# Shield_Bot.net
KiCad netlist of a schematic drawn in EAGLE
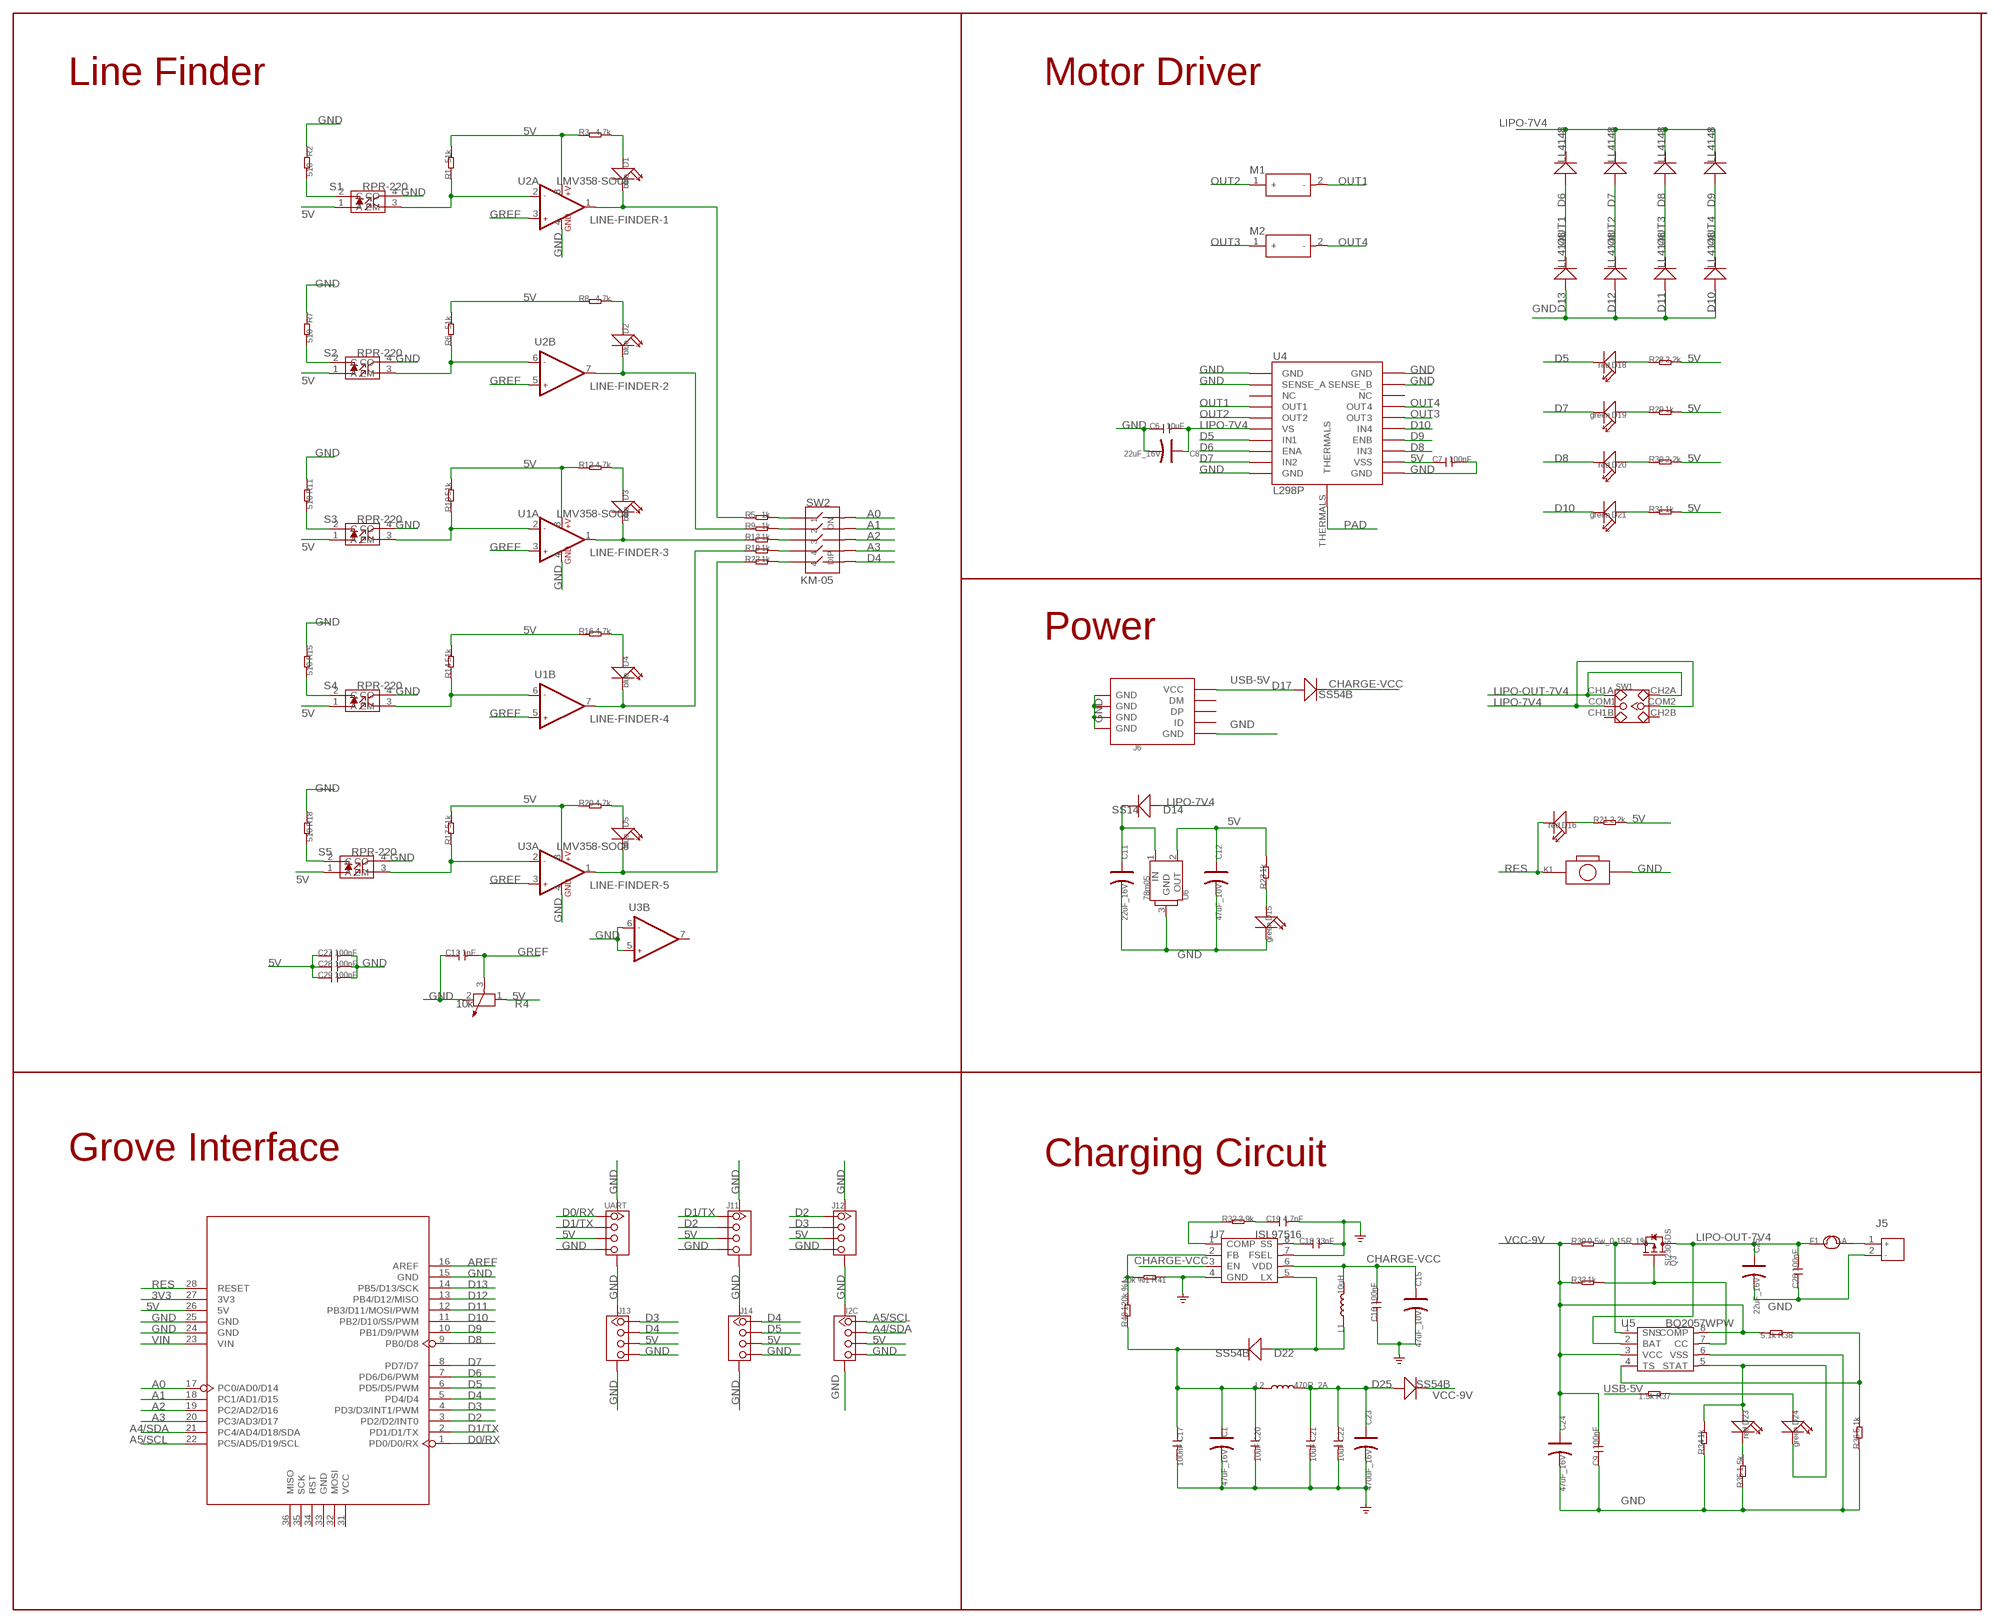
[diagram p0: schematic, sheet 1]

(export (version "E")
  (design (tool "Eeschema 10.0.6"))
  (components
    (comp (ref "C1")
      (value "47uF_16V")
      (footprint "eagle-import:AVX-C")
      (libsource (lib "eagle-import") (part "CAP-AVX-C"))
    )
    (comp (ref "C6")
      (value "10uF")
      (footprint "eagle-import:C0603")
      (libsource (lib "eagle-import") (part "C-0603"))
    )
    (comp (ref "C7")
      (value "100nF")
      (footprint "eagle-import:C0603")
      (libsource (lib "eagle-import") (part "C-0603"))
    )
    (comp (ref "C8")
      (value "22uF_16V")
      (footprint "eagle-import:AVX-B")
      (libsource (lib "eagle-import") (part "CAP-AVX-B"))
    )
    (comp (ref "C9")
      (value "100nF")
      (footprint "eagle-import:C0603")
      (libsource (lib "eagle-import") (part "C-0603"))
    )
    (comp (ref "C11")
      (value "22uF_16V")
      (footprint "eagle-import:AVX-B")
      (libsource (lib "eagle-import") (part "CAP-AVX-B"))
    )
    (comp (ref "C12")
      (value "47uF_10V")
      (footprint "eagle-import:AVX-B")
      (libsource (lib "eagle-import") (part "CAP-AVX-B"))
    )
    (comp (ref "C13")
      (value "1nF")
      (footprint "eagle-import:C0603")
      (libsource (lib "eagle-import") (part "C-0603"))
    )
    (comp (ref "C15")
      (value "47uF_10V")
      (footprint "eagle-import:AVX-B")
      (libsource (lib "eagle-import") (part "CAP-AVX-B"))
    )
    (comp (ref "C16")
      (value "100nF")
      (footprint "eagle-import:C0603")
      (libsource (lib "eagle-import") (part "C-0603"))
    )
    (comp (ref "C17")
      (value "100nF")
      (footprint "eagle-import:C0603")
      (libsource (lib "eagle-import") (part "C-0603"))
    )
    (comp (ref "C18")
      (value "33nF")
      (footprint "eagle-import:C0603")
      (libsource (lib "eagle-import") (part "C-0603"))
    )
    (comp (ref "C19")
      (value "4.7nF")
      (footprint "eagle-import:C0603")
      (libsource (lib "eagle-import") (part "C-0603"))
    )
    (comp (ref "C20")
      (value "10uF")
      (footprint "eagle-import:C0603")
      (libsource (lib "eagle-import") (part "C-0603"))
    )
    (comp (ref "C21")
      (value "10uF")
      (footprint "eagle-import:C0603")
      (libsource (lib "eagle-import") (part "C-0603"))
    )
    (comp (ref "C22")
      (value "10uF")
      (footprint "eagle-import:C0603")
      (libsource (lib "eagle-import") (part "C-0603"))
    )
    (comp (ref "C23")
      (value "470uF_16V")
      (footprint "eagle-import:AVX-E")
      (libsource (lib "eagle-import") (part "CAP-AVX-E"))
    )
    (comp (ref "C24")
      (value "47uF_16V")
      (footprint "eagle-import:AVX-C")
      (libsource (lib "eagle-import") (part "CAP-AVX-C"))
    )
    (comp (ref "C25")
      (value "22uF_16V")
      (footprint "eagle-import:AVX-B")
      (libsource (lib "eagle-import") (part "CAP-AVX-B"))
    )
    (comp (ref "C26")
      (value "100nF")
      (footprint "eagle-import:C0603")
      (libsource (lib "eagle-import") (part "C-0603"))
    )
    (comp (ref "C27")
      (value "100nF")
      (footprint "eagle-import:C0603")
      (libsource (lib "eagle-import") (part "C-0603"))
    )
    (comp (ref "C28")
      (value "100nF")
      (footprint "eagle-import:C0603")
      (libsource (lib "eagle-import") (part "C-0603"))
    )
    (comp (ref "C29")
      (value "100nF")
      (footprint "eagle-import:C0603")
      (libsource (lib "eagle-import") (part "C-0603"))
    )
    (comp (ref "D1")
      (value "blue")
      (footprint "eagle-import:LED-0603")
      (libsource (lib "eagle-import") (part "LED'0603'"))
    )
    (comp (ref "D2")
      (value "blue")
      (footprint "eagle-import:LED-0603")
      (libsource (lib "eagle-import") (part "LED'0603'"))
    )
    (comp (ref "D3")
      (value "blue")
      (footprint "eagle-import:LED-0603")
      (libsource (lib "eagle-import") (part "LED'0603'"))
    )
    (comp (ref "D4")
      (value "blue")
      (footprint "eagle-import:LED-0603")
      (libsource (lib "eagle-import") (part "LED'0603'"))
    )
    (comp (ref "D5")
      (value "blue")
      (footprint "eagle-import:LED-0603")
      (libsource (lib "eagle-import") (part "LED'0603'"))
    )
    (comp (ref "D6")
      (value "LL4148")
      (footprint "eagle-import:SOD123")
      (libsource (lib "eagle-import") (part "D'1206'"))
    )
    (comp (ref "D7")
      (value "LL4148")
      (footprint "eagle-import:SOD123")
      (libsource (lib "eagle-import") (part "D'1206'"))
    )
    (comp (ref "D8")
      (value "LL4148")
      (footprint "eagle-import:SOD123")
      (libsource (lib "eagle-import") (part "D'1206'"))
    )
    (comp (ref "D9")
      (value "LL4148")
      (footprint "eagle-import:SOD123")
      (libsource (lib "eagle-import") (part "D'1206'"))
    )
    (comp (ref "D10")
      (value "LL4148")
      (footprint "eagle-import:SOD123")
      (libsource (lib "eagle-import") (part "D'1206'"))
    )
    (comp (ref "D11")
      (value "LL4148")
      (footprint "eagle-import:SOD123")
      (libsource (lib "eagle-import") (part "D'1206'"))
    )
    (comp (ref "D12")
      (value "LL4148")
      (footprint "eagle-import:SOD123")
      (libsource (lib "eagle-import") (part "D'1206'"))
    )
    (comp (ref "D13")
      (value "LL4148")
      (footprint "eagle-import:SOD123")
      (libsource (lib "eagle-import") (part "D'1206'"))
    )
    (comp (ref "D14")
      (value "SS14")
      (footprint "eagle-import:D2010")
      (libsource (lib "eagle-import") (part "D'SMA'"))
    )
    (comp (ref "D15")
      (value "green")
      (footprint "eagle-import:LED-0603")
      (libsource (lib "eagle-import") (part "LED'0603'"))
    )
    (comp (ref "D16")
      (value "red")
      (footprint "eagle-import:LED-0603")
      (libsource (lib "eagle-import") (part "LED'0603'"))
    )
    (comp (ref "D17")
      (value "SS54B")
      (footprint "eagle-import:SMB")
      (libsource (lib "eagle-import") (part "D'MBRS240LT3'"))
    )
    (comp (ref "D18")
      (value "red")
      (footprint "eagle-import:LED-0603")
      (libsource (lib "eagle-import") (part "LED'0603'"))
    )
    (comp (ref "D19")
      (value "green")
      (footprint "eagle-import:LED-0603")
      (libsource (lib "eagle-import") (part "LED'0603'"))
    )
    (comp (ref "D20")
      (value "red")
      (footprint "eagle-import:LED-0603")
      (libsource (lib "eagle-import") (part "LED'0603'"))
    )
    (comp (ref "D21")
      (value "green")
      (footprint "eagle-import:LED-0603")
      (libsource (lib "eagle-import") (part "LED'0603'"))
    )
    (comp (ref "D22")
      (value "SS54B")
      (footprint "eagle-import:SMB")
      (libsource (lib "eagle-import") (part "D'MBRS240LT3'"))
    )
    (comp (ref "D23")
      (value "red")
      (footprint "eagle-import:LED-0603")
      (libsource (lib "eagle-import") (part "LED'0603'"))
    )
    (comp (ref "D24")
      (value "green")
      (footprint "eagle-import:LED-0603")
      (libsource (lib "eagle-import") (part "LED'0603'"))
    )
    (comp (ref "D25")
      (value "SS54B")
      (footprint "eagle-import:SMB")
      (libsource (lib "eagle-import") (part "D'MBRS240LT3'"))
    )
    (comp (ref "F1")
      (value "1A")
      (footprint "eagle-import:1812")
      (libsource (lib "eagle-import") (part "FUSE"))
    )
    (comp (ref "I2C")
      (value "TWIG-4P-2.0-SMD-FEMALE-REINFORCE'90D'")
      (footprint "eagle-import:4P-SMD-2.0-90D")
      (libsource (lib "eagle-import") (part "TWIG-4P-2.0-SMD-FEMALE-REINFORCE'90D'"))
    )
    (comp (ref "J5")
      (value "JACK-JST-2P-PW'2.0'")
      (footprint "eagle-import:JST-2.0")
      (libsource (lib "eagle-import") (part "JACK-JST-2P-PW'2.0'"))
    )
    (comp (ref "J6")
      (value "USB-MINIUSB-5P-STRONG")
      (footprint "eagle-import:MINI-SMD-5P")
      (libsource (lib "eagle-import") (part "USB-MINIUSB-5P-STRONG"))
    )
    (comp (ref "J11")
      (value "TWIG-4P-2.0-SMD-FEMALE-REINFORCE'90D'")
      (footprint "eagle-import:4P-SMD-2.0-90D")
      (libsource (lib "eagle-import") (part "TWIG-4P-2.0-SMD-FEMALE-REINFORCE'90D'"))
    )
    (comp (ref "J12")
      (value "TWIG-4P-2.0-SMD-FEMALE-REINFORCE'90D'")
      (footprint "eagle-import:4P-SMD-2.0-90D")
      (libsource (lib "eagle-import") (part "TWIG-4P-2.0-SMD-FEMALE-REINFORCE'90D'"))
    )
    (comp (ref "J13")
      (value "TWIG-4P-2.0-SMD-FEMALE-REINFORCE'90D'")
      (footprint "eagle-import:4P-SMD-2.0-90D")
      (libsource (lib "eagle-import") (part "TWIG-4P-2.0-SMD-FEMALE-REINFORCE'90D'"))
    )
    (comp (ref "J14")
      (value "TWIG-4P-2.0-SMD-FEMALE-REINFORCE'90D'")
      (footprint "eagle-import:4P-SMD-2.0-90D")
      (libsource (lib "eagle-import") (part "TWIG-4P-2.0-SMD-FEMALE-REINFORCE'90D'"))
    )
    (comp (ref "K1")
      (value "BOTTON-2P-90D")
      (footprint "eagle-import:2P-7.62X3.56-90D")
      (libsource (lib "eagle-import") (part "BOTTON-2P-90D"))
    )
    (comp (ref "L1")
      (value "10uH")
      (footprint "eagle-import:2626")
      (libsource (lib "eagle-import") (part "L'IHLP-2525BD-01'"))
    )
    (comp (ref "L2")
      (value "470R_2A")
      (footprint "eagle-import:L0805")
      (libsource (lib "eagle-import") (part "L'0805'"))
    )
    (comp (ref "M1")
      (value "MOTOR-2P-PAD")
      (footprint "eagle-import:2P-SMD-27X26")
      (libsource (lib "eagle-import") (part "MOTOR-2P-PAD"))
    )
    (comp (ref "M2")
      (value "MOTOR-2P-PAD")
      (footprint "eagle-import:2P-SMD-27X26")
      (libsource (lib "eagle-import") (part "MOTOR-2P-PAD"))
    )
    (comp (ref "Q3")
      (value "SI2305DS")
      (footprint "eagle-import:SOT23")
      (libsource (lib "eagle-import") (part "MOSFET-P'SI2323CDS/SI2305DS{lt}BR{gt}'"))
    )
    (comp (ref "R1")
      (value "51k")
      (footprint "eagle-import:R0603")
      (libsource (lib "eagle-import") (part "R-0603"))
    )
    (comp (ref "R2")
      (value "510")
      (footprint "eagle-import:R0603")
      (libsource (lib "eagle-import") (part "R-0603"))
    )
    (comp (ref "R3")
      (value "4.7k")
      (footprint "eagle-import:R0603")
      (libsource (lib "eagle-import") (part "R-0603"))
    )
    (comp (ref "R4")
      (value "10k")
      (footprint "eagle-import:3P-SQUA-7X6.8")
      (libsource (lib "eagle-import") (part "R-POTENTIOMETER'3362'"))
    )
    (comp (ref "R5")
      (value "1k")
      (footprint "eagle-import:R0603")
      (libsource (lib "eagle-import") (part "R-0603"))
    )
    (comp (ref "R6")
      (value "51k")
      (footprint "eagle-import:R0603")
      (libsource (lib "eagle-import") (part "R-0603"))
    )
    (comp (ref "R7")
      (value "510")
      (footprint "eagle-import:R0603")
      (libsource (lib "eagle-import") (part "R-0603"))
    )
    (comp (ref "R8")
      (value "4.7k")
      (footprint "eagle-import:R0603")
      (libsource (lib "eagle-import") (part "R-0603"))
    )
    (comp (ref "R9")
      (value "1k")
      (footprint "eagle-import:R0603")
      (libsource (lib "eagle-import") (part "R-0603"))
    )
    (comp (ref "R10")
      (value "51k")
      (footprint "eagle-import:R0603")
      (libsource (lib "eagle-import") (part "R-0603"))
    )
    (comp (ref "R11")
      (value "510")
      (footprint "eagle-import:R0603")
      (libsource (lib "eagle-import") (part "R-0603"))
    )
    (comp (ref "R12")
      (value "4.7k")
      (footprint "eagle-import:R0603")
      (libsource (lib "eagle-import") (part "R-0603"))
    )
    (comp (ref "R13")
      (value "1k")
      (footprint "eagle-import:R0603")
      (libsource (lib "eagle-import") (part "R-0603"))
    )
    (comp (ref "R14")
      (value "51k")
      (footprint "eagle-import:R0603")
      (libsource (lib "eagle-import") (part "R-0603"))
    )
    (comp (ref "R15")
      (value "510")
      (footprint "eagle-import:R0603")
      (libsource (lib "eagle-import") (part "R-0603"))
    )
    (comp (ref "R16")
      (value "4.7k")
      (footprint "eagle-import:R0603")
      (libsource (lib "eagle-import") (part "R-0603"))
    )
    (comp (ref "R17")
      (value "51k")
      (footprint "eagle-import:R0603")
      (libsource (lib "eagle-import") (part "R-0603"))
    )
    (comp (ref "R18")
      (value "510")
      (footprint "eagle-import:R0603")
      (libsource (lib "eagle-import") (part "R-0603"))
    )
    (comp (ref "R19")
      (value "1k")
      (footprint "eagle-import:R0603")
      (libsource (lib "eagle-import") (part "R-0603"))
    )
    (comp (ref "R20")
      (value "4.7k")
      (footprint "eagle-import:R0603")
      (libsource (lib "eagle-import") (part "R-0603"))
    )
    (comp (ref "R21")
      (value "2.2k")
      (footprint "eagle-import:R0603")
      (libsource (lib "eagle-import") (part "R-0603"))
    )
    (comp (ref "R22")
      (value "1k")
      (footprint "eagle-import:R0603")
      (libsource (lib "eagle-import") (part "R-0603"))
    )
    (comp (ref "R23")
      (value "1k")
      (footprint "eagle-import:R0603")
      (libsource (lib "eagle-import") (part "R-0603"))
    )
    (comp (ref "R28")
      (value "2.2k")
      (footprint "eagle-import:R0603")
      (libsource (lib "eagle-import") (part "R-0603"))
    )
    (comp (ref "R29")
      (value "1k")
      (footprint "eagle-import:R0603")
      (libsource (lib "eagle-import") (part "R-0603"))
    )
    (comp (ref "R30")
      (value "2.2k")
      (footprint "eagle-import:R0603")
      (libsource (lib "eagle-import") (part "R-0603"))
    )
    (comp (ref "R31")
      (value "1k")
      (footprint "eagle-import:R0603")
      (libsource (lib "eagle-import") (part "R-0603"))
    )
    (comp (ref "R32")
      (value "3.9k")
      (footprint "eagle-import:R0603")
      (libsource (lib "eagle-import") (part "R-0603"))
    )
    (comp (ref "R33")
      (value "1k")
      (footprint "eagle-import:R0603")
      (libsource (lib "eagle-import") (part "R-0603"))
    )
    (comp (ref "R34")
      (value "1k")
      (footprint "eagle-import:R0603")
      (libsource (lib "eagle-import") (part "R-0603"))
    )
    (comp (ref "R35")
      (value "1.5k")
      (footprint "eagle-import:R0603")
      (libsource (lib "eagle-import") (part "R-0603"))
    )
    (comp (ref "R36")
      (value "5.1k")
      (footprint "eagle-import:R0603")
      (libsource (lib "eagle-import") (part "R-0603"))
    )
    (comp (ref "R37")
      (value "1.5k")
      (footprint "eagle-import:R0603")
      (libsource (lib "eagle-import") (part "R-0603"))
    )
    (comp (ref "R38")
      (value "5.1k")
      (footprint "eagle-import:R0603")
      (libsource (lib "eagle-import") (part "R-0603"))
    )
    (comp (ref "R39")
      (value "0.5w_0.15R 1%")
      (footprint "eagle-import:R2512")
      (libsource (lib "eagle-import") (part "R-2512"))
    )
    (comp (ref "R40")
      (value "120k %1")
      (footprint "eagle-import:R0603")
      (libsource (lib "eagle-import") (part "R-0603"))
    )
    (comp (ref "R41")
      (value "20k %1")
      (footprint "eagle-import:R0603")
      (libsource (lib "eagle-import") (part "R-0603"))
    )
    (comp (ref "S1")
      (value "RPR-220")
      (footprint "eagle-import:4P-6.4X4.9X6.5H")
      (libsource (lib "eagle-import") (part "REFLECTIVE-PHOTOSENSOR-RPR-220"))
    )
    (comp (ref "S2")
      (value "RPR-220")
      (footprint "eagle-import:4P-6.4X4.9X6.5H")
      (libsource (lib "eagle-import") (part "REFLECTIVE-PHOTOSENSOR-RPR-220"))
    )
    (comp (ref "S3")
      (value "RPR-220")
      (footprint "eagle-import:4P-6.4X4.9X6.5H")
      (libsource (lib "eagle-import") (part "REFLECTIVE-PHOTOSENSOR-RPR-220"))
    )
    (comp (ref "S4")
      (value "RPR-220")
      (footprint "eagle-import:4P-6.4X4.9X6.5H")
      (libsource (lib "eagle-import") (part "REFLECTIVE-PHOTOSENSOR-RPR-220"))
    )
    (comp (ref "S5")
      (value "RPR-220")
      (footprint "eagle-import:4P-6.4X4.9X6.5H")
      (libsource (lib "eagle-import") (part "REFLECTIVE-PHOTOSENSOR-RPR-220"))
    )
    (comp (ref "SW1")
      (value "SWITCH-2CH-6P'90D'")
      (footprint "eagle-import:6P-2CH-2.54-9.0X3.6-90D")
      (libsource (lib "eagle-import") (part "SWITCH-2CH-6P'90D'"))
    )
    (comp (ref "SW2")
      (value "KM-05")
      (footprint "eagle-import:10P-SMD-14.2X6.8")
      (libsource (lib "eagle-import") (part "SWITCH-KM-05-10P"))
    )
    (comp (ref "U1")
      (value "LMV358-SO08")
      (footprint "eagle-import:SO08")
      (libsource (lib "eagle-import") (part "LMV358-SO08"))
    )
    (comp (ref "U2")
      (value "LMV358-SO08")
      (footprint "eagle-import:SO08")
      (libsource (lib "eagle-import") (part "LMV358-SO08"))
    )
    (comp (ref "U3")
      (value "LMV358-SO08")
      (footprint "eagle-import:SO08")
      (libsource (lib "eagle-import") (part "LMV358-SO08"))
    )
    (comp (ref "U4")
      (value "L298P")
      (footprint "eagle-import:POWERSO20")
      (libsource (lib "eagle-import") (part "L298_BRIDGE_DRIVER"))
    )
    (comp (ref "U5")
      (value "BQ2057WPW")
      (footprint "eagle-import:TSSOP8")
      (libsource (lib "eagle-import") (part "BQ2057WPW"))
    )
    (comp (ref "U6")
      (value "78m05")
      (footprint "eagle-import:TO252")
      (libsource (lib "eagle-import") (part "78M05-TO252"))
    )
    (comp (ref "U7")
      (value "ISL97516")
      (footprint "eagle-import:MSOP8")
      (libsource (lib "eagle-import") (part "ISL97516"))
    )
    (comp (ref "U13")
      (value "ARDUINO")
      (footprint "eagle-import:ARDUINO")
      (libsource (lib "eagle-import") (part "ARDUINO"))
    )
    (comp (ref "UART")
      (value "TWIG-4P-2.0-SMD-FEMALE-REINFORCE'90D'")
      (footprint "eagle-import:4P-SMD-2.0-90D")
      (libsource (lib "eagle-import") (part "TWIG-4P-2.0-SMD-FEMALE-REINFORCE'90D'"))
    )
  )
  (nets
    (net (code "1") (name "/3V3") (class "Default")
      (node (ref "U13") (pin "27") (pinfunction "3V3_27") (pintype "bidirectional"))
    )
    (net (code "2") (name "/5V") (class "Default")
      (node (ref "C12") (pin "+") (pinfunction "+_+") (pintype "passive"))
      (node (ref "C27") (pin "1") (pinfunction "1_1") (pintype "passive"))
      (node (ref "C28") (pin "1") (pinfunction "1_1") (pintype "passive"))
      (node (ref "C29") (pin "1") (pinfunction "1_1") (pintype "passive"))
      (node (ref "C7") (pin "1") (pinfunction "1_1") (pintype "passive"))
      (node (ref "I2C") (pin "3") (pinfunction "3_3") (pintype "bidirectional"))
      (node (ref "J11") (pin "3") (pinfunction "3_3") (pintype "bidirectional"))
      (node (ref "J12") (pin "3") (pinfunction "3_3") (pintype "bidirectional"))
      (node (ref "J13") (pin "3") (pinfunction "3_3") (pintype "bidirectional"))
      (node (ref "J14") (pin "3") (pinfunction "3_3") (pintype "bidirectional"))
      (node (ref "R1") (pin "2") (pinfunction "2_2") (pintype "passive"))
      (node (ref "R10") (pin "2") (pinfunction "2_2") (pintype "passive"))
      (node (ref "R12") (pin "1") (pinfunction "1_1") (pintype "passive"))
      (node (ref "R14") (pin "2") (pinfunction "2_2") (pintype "passive"))
      (node (ref "R16") (pin "1") (pinfunction "1_1") (pintype "passive"))
      (node (ref "R17") (pin "2") (pinfunction "2_2") (pintype "passive"))
      (node (ref "R20") (pin "1") (pinfunction "1_1") (pintype "passive"))
      (node (ref "R21") (pin "2") (pinfunction "2_2") (pintype "passive"))
      (node (ref "R23") (pin "2") (pinfunction "2_2") (pintype "passive"))
      (node (ref "R28") (pin "2") (pinfunction "2_2") (pintype "passive"))
      (node (ref "R29") (pin "2") (pinfunction "2_2") (pintype "passive"))
      (node (ref "R3") (pin "1") (pinfunction "1_1") (pintype "passive"))
      (node (ref "R30") (pin "2") (pinfunction "2_2") (pintype "passive"))
      (node (ref "R31") (pin "2") (pinfunction "2_2") (pintype "passive"))
      (node (ref "R4") (pin "1") (pinfunction "1_1") (pintype "passive"))
      (node (ref "R6") (pin "2") (pinfunction "2_2") (pintype "passive"))
      (node (ref "R8") (pin "1") (pinfunction "1_1") (pintype "passive"))
      (node (ref "S1") (pin "1") (pinfunction "A_1") (pintype "bidirectional"))
      (node (ref "S2") (pin "1") (pinfunction "A_1") (pintype "bidirectional"))
      (node (ref "S3") (pin "1") (pinfunction "A_1") (pintype "bidirectional"))
      (node (ref "S4") (pin "1") (pinfunction "A_1") (pintype "bidirectional"))
      (node (ref "S5") (pin "1") (pinfunction "A_1") (pintype "bidirectional"))
      (node (ref "U1") (pin "8") (pinfunction "+V_8") (pintype "power_in"))
      (node (ref "U13") (pin "26") (pinfunction "5V_26") (pintype "bidirectional"))
      (node (ref "U2") (pin "8") (pinfunction "+V_8") (pintype "power_in"))
      (node (ref "U3") (pin "8") (pinfunction "+V_8") (pintype "power_in"))
      (node (ref "U4") (pin "P$12") (pinfunction "VSS_P$12") (pintype "bidirectional"))
      (node (ref "U6") (pin "2") (pinfunction "OUT_2") (pintype "bidirectional"))
      (node (ref "UART") (pin "3") (pinfunction "3_3") (pintype "bidirectional"))
    )
    (net (code "3") (name "/A0") (class "Default")
      (node (ref "SW2") (pin "10") (pinfunction "10_10") (pintype "bidirectional"))
      (node (ref "U13") (pin "17") (pinfunction "PC0/AD0/D14_17") (pintype "bidirectional"))
    )
    (net (code "4") (name "/A1") (class "Default")
      (node (ref "SW2") (pin "9") (pinfunction "9_9") (pintype "bidirectional"))
      (node (ref "U13") (pin "18") (pinfunction "PC1/AD1/D15_18") (pintype "bidirectional"))
    )
    (net (code "5") (name "/A2") (class "Default")
      (node (ref "SW2") (pin "8") (pinfunction "8_8") (pintype "bidirectional"))
      (node (ref "U13") (pin "19") (pinfunction "PC2/AD2/D16_19") (pintype "bidirectional"))
    )
    (net (code "6") (name "/A3") (class "Default")
      (node (ref "SW2") (pin "7") (pinfunction "7_7") (pintype "bidirectional"))
      (node (ref "U13") (pin "20") (pinfunction "PC3/AD3/D17_20") (pintype "bidirectional"))
    )
    (net (code "7") (name "/A4{slash}SDA") (class "Default")
      (node (ref "I2C") (pin "2") (pinfunction "2_2") (pintype "bidirectional"))
      (node (ref "U13") (pin "21") (pinfunction "PC4/AD4/D18/SDA_21") (pintype "bidirectional"))
    )
    (net (code "8") (name "/A5{slash}SCL") (class "Default")
      (node (ref "I2C") (pin "1") (pinfunction "1_1") (pintype "bidirectional"))
      (node (ref "U13") (pin "22") (pinfunction "PC5/AD5/D19/SCL_22") (pintype "bidirectional"))
    )
    (net (code "9") (name "/AREF") (class "Default")
      (node (ref "U13") (pin "16") (pinfunction "AREF_16") (pintype "bidirectional"))
    )
    (net (code "10") (name "/CHARGE-VCC") (class "Default")
      (node (ref "C15") (pin "+") (pinfunction "+_+") (pintype "passive"))
      (node (ref "C16") (pin "2") (pinfunction "2_2") (pintype "passive"))
      (node (ref "D17") (pin "-") (pinfunction "-_-") (pintype "passive"))
      (node (ref "L1") (pin "2") (pinfunction "2_2") (pintype "passive"))
      (node (ref "U7") (pin "3") (pinfunction "EN_3") (pintype "input"))
      (node (ref "U7") (pin "6") (pinfunction "VDD_6") (pintype "power_in"))
    )
    (net (code "11") (name "/D0{slash}RX") (class "Default")
      (node (ref "U13") (pin "1") (pinfunction "PD0/D0/RX_1") (pintype "bidirectional"))
      (node (ref "UART") (pin "1") (pinfunction "1_1") (pintype "bidirectional"))
    )
    (net (code "12") (name "/D1{slash}TX") (class "Default")
      (node (ref "J11") (pin "1") (pinfunction "1_1") (pintype "bidirectional"))
      (node (ref "U13") (pin "2") (pinfunction "PD1/D1/TX_2") (pintype "bidirectional"))
      (node (ref "UART") (pin "2") (pinfunction "2_2") (pintype "bidirectional"))
    )
    (net (code "13") (name "/D2") (class "Default")
      (node (ref "J11") (pin "2") (pinfunction "2_2") (pintype "bidirectional"))
      (node (ref "J12") (pin "1") (pinfunction "1_1") (pintype "bidirectional"))
      (node (ref "U13") (pin "3") (pinfunction "PD2/D2/INT0_3") (pintype "bidirectional"))
    )
    (net (code "14") (name "/D3") (class "Default")
      (node (ref "J12") (pin "2") (pinfunction "2_2") (pintype "bidirectional"))
      (node (ref "J13") (pin "1") (pinfunction "1_1") (pintype "bidirectional"))
      (node (ref "U13") (pin "4") (pinfunction "PD3/D3/INT1/PWM_4") (pintype "bidirectional"))
    )
    (net (code "15") (name "/D4") (class "Default")
      (node (ref "J13") (pin "2") (pinfunction "2_2") (pintype "bidirectional"))
      (node (ref "J14") (pin "1") (pinfunction "1_1") (pintype "bidirectional"))
      (node (ref "SW2") (pin "6") (pinfunction "6_6") (pintype "bidirectional"))
      (node (ref "U13") (pin "5") (pinfunction "PD4/D4_5") (pintype "bidirectional"))
    )
    (net (code "16") (name "/D5") (class "Default")
      (node (ref "D18") (pin "-") (pinfunction "-_-") (pintype "passive"))
      (node (ref "J14") (pin "2") (pinfunction "2_2") (pintype "bidirectional"))
      (node (ref "U13") (pin "6") (pinfunction "PD5/D5/PWM_6") (pintype "bidirectional"))
      (node (ref "U4") (pin "P$7") (pinfunction "IN1_P$7") (pintype "bidirectional"))
    )
    (net (code "17") (name "/D6") (class "Default")
      (node (ref "U13") (pin "7") (pinfunction "PD6/D6/PWM_7") (pintype "bidirectional"))
      (node (ref "U4") (pin "P$8") (pinfunction "ENA_P$8") (pintype "bidirectional"))
    )
    (net (code "18") (name "/D7") (class "Default")
      (node (ref "D19") (pin "-") (pinfunction "-_-") (pintype "passive"))
      (node (ref "U13") (pin "8") (pinfunction "PD7/D7_8") (pintype "bidirectional"))
      (node (ref "U4") (pin "P$9") (pinfunction "IN2_P$9") (pintype "bidirectional"))
    )
    (net (code "19") (name "/D8") (class "Default")
      (node (ref "D20") (pin "-") (pinfunction "-_-") (pintype "passive"))
      (node (ref "U13") (pin "9") (pinfunction "PB0/D8_9") (pintype "bidirectional"))
      (node (ref "U4") (pin "P$13") (pinfunction "IN3_P$13") (pintype "bidirectional"))
    )
    (net (code "20") (name "/D9") (class "Default")
      (node (ref "U13") (pin "10") (pinfunction "PB1/D9/PWM_10") (pintype "bidirectional"))
      (node (ref "U4") (pin "P$14") (pinfunction "ENB_P$14") (pintype "bidirectional"))
    )
    (net (code "21") (name "/D10") (class "Default")
      (node (ref "D21") (pin "-") (pinfunction "-_-") (pintype "passive"))
      (node (ref "U13") (pin "11") (pinfunction "PB2/D10/SS/PWM_11") (pintype "bidirectional"))
      (node (ref "U4") (pin "P$15") (pinfunction "IN4_P$15") (pintype "bidirectional"))
    )
    (net (code "22") (name "/D11") (class "Default")
      (node (ref "U13") (pin "12") (pinfunction "PB3/D11/MOSI/PWM_12") (pintype "bidirectional"))
    )
    (net (code "23") (name "/D12") (class "Default")
      (node (ref "U13") (pin "13") (pinfunction "PB4/D12/MISO_13") (pintype "bidirectional"))
    )
    (net (code "24") (name "/D13") (class "Default")
      (node (ref "U13") (pin "14") (pinfunction "PB5/D13/SCK_14") (pintype "bidirectional"))
    )
    (net (code "25") (name "/GREF") (class "Default")
      (node (ref "C13") (pin "2") (pinfunction "2_2") (pintype "passive"))
      (node (ref "R4") (pin "3") (pinfunction "3_3") (pintype "passive"))
      (node (ref "U1") (pin "3") (pinfunction "+IN1_3") (pintype "input"))
      (node (ref "U1") (pin "5") (pinfunction "+IN2_5") (pintype "input"))
      (node (ref "U2") (pin "3") (pinfunction "+IN1_3") (pintype "input"))
      (node (ref "U2") (pin "5") (pinfunction "+IN2_5") (pintype "input"))
      (node (ref "U3") (pin "3") (pinfunction "+IN1_3") (pintype "input"))
    )
    (net (code "26") (name "/LINE-FINDER-1") (class "Default")
      (node (ref "D1") (pin "-") (pinfunction "-_-") (pintype "passive"))
      (node (ref "R5") (pin "1") (pinfunction "1_1") (pintype "passive"))
      (node (ref "U2") (pin "1") (pinfunction "OUT1_1") (pintype "output"))
    )
    (net (code "27") (name "/LINE-FINDER-2") (class "Default")
      (node (ref "D2") (pin "-") (pinfunction "-_-") (pintype "passive"))
      (node (ref "R9") (pin "1") (pinfunction "1_1") (pintype "passive"))
      (node (ref "U2") (pin "7") (pinfunction "OUT2_7") (pintype "output"))
    )
    (net (code "28") (name "/LINE-FINDER-3") (class "Default")
      (node (ref "D3") (pin "-") (pinfunction "-_-") (pintype "passive"))
      (node (ref "R13") (pin "1") (pinfunction "1_1") (pintype "passive"))
      (node (ref "U1") (pin "1") (pinfunction "OUT1_1") (pintype "output"))
    )
    (net (code "29") (name "/LINE-FINDER-4") (class "Default")
      (node (ref "D4") (pin "-") (pinfunction "-_-") (pintype "passive"))
      (node (ref "R19") (pin "1") (pinfunction "1_1") (pintype "passive"))
      (node (ref "U1") (pin "7") (pinfunction "OUT2_7") (pintype "output"))
    )
    (net (code "30") (name "/LINE-FINDER-5") (class "Default")
      (node (ref "D5") (pin "-") (pinfunction "-_-") (pintype "passive"))
      (node (ref "R22") (pin "1") (pinfunction "1_1") (pintype "passive"))
      (node (ref "U3") (pin "1") (pinfunction "OUT1_1") (pintype "output"))
    )
    (net (code "31") (name "/LIPO-7V4") (class "Default")
      (node (ref "C6") (pin "2") (pinfunction "2_2") (pintype "passive"))
      (node (ref "C8") (pin "+") (pinfunction "+_+") (pintype "passive"))
      (node (ref "D14") (pin "+") (pinfunction "+_+") (pintype "passive"))
      (node (ref "D6") (pin "-") (pinfunction "-_-") (pintype "passive"))
      (node (ref "D7") (pin "-") (pinfunction "-_-") (pintype "passive"))
      (node (ref "D8") (pin "-") (pinfunction "-_-") (pintype "passive"))
      (node (ref "D9") (pin "-") (pinfunction "-_-") (pintype "passive"))
      (node (ref "SW1") (pin "COM1") (pinfunction "COM1_COM1") (pintype "bidirectional"))
      (node (ref "SW1") (pin "COM2") (pinfunction "COM2_COM2") (pintype "bidirectional"))
      (node (ref "U4") (pin "P$6") (pinfunction "VS_P$6") (pintype "bidirectional"))
    )
    (net (code "32") (name "/LIPO-OUT-7V4") (class "Default")
      (node (ref "C25") (pin "+") (pinfunction "+_+") (pintype "passive"))
      (node (ref "C26") (pin "2") (pinfunction "2_2") (pintype "passive"))
      (node (ref "F1") (pin "1") (pinfunction "1_1") (pintype "bidirectional"))
      (node (ref "Q3") (pin "3") (pinfunction "D_3") (pintype "passive"))
      (node (ref "SW1") (pin "CH1A") (pinfunction "CH1A_CH1A") (pintype "bidirectional"))
      (node (ref "SW1") (pin "CH2A") (pinfunction "CH2A_CH2A") (pintype "bidirectional"))
      (node (ref "U5") (pin "2") (pinfunction "BAT_2") (pintype "input"))
    )
    (net (code "33") (name "/OUT1") (class "Default")
      (node (ref "D13") (pin "-") (pinfunction "-_-") (pintype "passive"))
      (node (ref "D6") (pin "+") (pinfunction "+_+") (pintype "passive"))
      (node (ref "M1") (pin "2") (pinfunction "-_2") (pintype "bidirectional"))
      (node (ref "U4") (pin "P$4") (pinfunction "OUT1_P$4") (pintype "bidirectional"))
    )
    (net (code "34") (name "/OUT2") (class "Default")
      (node (ref "D12") (pin "-") (pinfunction "-_-") (pintype "passive"))
      (node (ref "D7") (pin "+") (pinfunction "+_+") (pintype "passive"))
      (node (ref "M1") (pin "1") (pinfunction "+_1") (pintype "bidirectional"))
      (node (ref "U4") (pin "P$5") (pinfunction "OUT2_P$5") (pintype "bidirectional"))
    )
    (net (code "35") (name "/OUT3") (class "Default")
      (node (ref "D11") (pin "-") (pinfunction "-_-") (pintype "passive"))
      (node (ref "D8") (pin "+") (pinfunction "+_+") (pintype "passive"))
      (node (ref "M2") (pin "1") (pinfunction "+_1") (pintype "bidirectional"))
      (node (ref "U4") (pin "P$16") (pinfunction "OUT3_P$16") (pintype "bidirectional"))
    )
    (net (code "36") (name "/OUT4") (class "Default")
      (node (ref "D10") (pin "-") (pinfunction "-_-") (pintype "passive"))
      (node (ref "D9") (pin "+") (pinfunction "+_+") (pintype "passive"))
      (node (ref "M2") (pin "2") (pinfunction "-_2") (pintype "bidirectional"))
      (node (ref "U4") (pin "P$17") (pinfunction "OUT4_P$17") (pintype "bidirectional"))
    )
    (net (code "37") (name "/PAD") (class "Default")
      (node (ref "U4") (pin "THERMALS") (pinfunction "THERMALS_THERMALS") (pintype "bidirectional"))
    )
    (net (code "38") (name "/RES") (class "Default")
      (node (ref "D16") (pin "-") (pinfunction "-_-") (pintype "passive"))
      (node (ref "K1") (pin "P$1") (pinfunction "1_P$1") (pintype "bidirectional"))
      (node (ref "U13") (pin "28") (pinfunction "RESET_28") (pintype "bidirectional"))
    )
    (net (code "39") (name "/USB-5V") (class "Default")
      (node (ref "D17") (pin "+") (pinfunction "+_+") (pintype "passive"))
      (node (ref "J6") (pin "1") (pinfunction "VCC_1") (pintype "bidirectional"))
      (node (ref "R37") (pin "2") (pinfunction "2_2") (pintype "passive"))
    )
    (net (code "40") (name "/VCC-9V") (class "Default")
      (node (ref "C24") (pin "+") (pinfunction "+_+") (pintype "passive"))
      (node (ref "C9") (pin "2") (pinfunction "2_2") (pintype "passive"))
      (node (ref "D25") (pin "-") (pinfunction "-_-") (pintype "passive"))
      (node (ref "R33") (pin "1") (pinfunction "1_1") (pintype "passive"))
      (node (ref "R38") (pin "2") (pinfunction "2_2") (pintype "passive"))
      (node (ref "R39") (pin "1") (pinfunction "1_1") (pintype "passive"))
      (node (ref "U5") (pin "3") (pinfunction "VCC_3") (pintype "input"))
      (node (ref "U5") (pin "8") (pinfunction "COMP_8") (pintype "input"))
    )
    (net (code "41") (name "/VIN") (class "Default")
      (node (ref "U13") (pin "23") (pinfunction "VIN_23") (pintype "bidirectional"))
    )
    (net (code "42") (name "GND_POWER") (class "Default")
      (node (ref "C1") (pin "-") (pinfunction "-_-") (pintype "passive"))
      (node (ref "C11") (pin "-") (pinfunction "-_-") (pintype "passive"))
      (node (ref "C12") (pin "-") (pinfunction "-_-") (pintype "passive"))
      (node (ref "C13") (pin "1") (pinfunction "1_1") (pintype "passive"))
      (node (ref "C15") (pin "-") (pinfunction "-_-") (pintype "passive"))
      (node (ref "C16") (pin "1") (pinfunction "1_1") (pintype "passive"))
      (node (ref "C17") (pin "2") (pinfunction "2_2") (pintype "passive"))
      (node (ref "C18") (pin "2") (pinfunction "2_2") (pintype "passive"))
      (node (ref "C19") (pin "2") (pinfunction "2_2") (pintype "passive"))
      (node (ref "C20") (pin "2") (pinfunction "2_2") (pintype "passive"))
      (node (ref "C21") (pin "2") (pinfunction "2_2") (pintype "passive"))
      (node (ref "C22") (pin "2") (pinfunction "2_2") (pintype "passive"))
      (node (ref "C23") (pin "-") (pinfunction "-_-") (pintype "passive"))
      (node (ref "C24") (pin "-") (pinfunction "-_-") (pintype "passive"))
      (node (ref "C25") (pin "-") (pinfunction "-_-") (pintype "passive"))
      (node (ref "C26") (pin "1") (pinfunction "1_1") (pintype "passive"))
      (node (ref "C27") (pin "2") (pinfunction "2_2") (pintype "passive"))
      (node (ref "C28") (pin "2") (pinfunction "2_2") (pintype "passive"))
      (node (ref "C29") (pin "2") (pinfunction "2_2") (pintype "passive"))
      (node (ref "C6") (pin "1") (pinfunction "1_1") (pintype "passive"))
      (node (ref "C7") (pin "2") (pinfunction "2_2") (pintype "passive"))
      (node (ref "C8") (pin "-") (pinfunction "-_-") (pintype "passive"))
      (node (ref "C9") (pin "1") (pinfunction "1_1") (pintype "passive"))
      (node (ref "D10") (pin "+") (pinfunction "+_+") (pintype "passive"))
      (node (ref "D11") (pin "+") (pinfunction "+_+") (pintype "passive"))
      (node (ref "D12") (pin "+") (pinfunction "+_+") (pintype "passive"))
      (node (ref "D13") (pin "+") (pinfunction "+_+") (pintype "passive"))
      (node (ref "D15") (pin "-") (pinfunction "-_-") (pintype "passive"))
      (node (ref "I2C") (pin "4") (pinfunction "4_4") (pintype "bidirectional"))
      (node (ref "I2C") (pin "SS1") (pinfunction "SS1_SS1") (pintype "bidirectional"))
      (node (ref "I2C") (pin "SS2") (pinfunction "SS2_SS2") (pintype "bidirectional"))
      (node (ref "J11") (pin "4") (pinfunction "4_4") (pintype "bidirectional"))
      (node (ref "J11") (pin "SS1") (pinfunction "SS1_SS1") (pintype "bidirectional"))
      (node (ref "J11") (pin "SS2") (pinfunction "SS2_SS2") (pintype "bidirectional"))
      (node (ref "J12") (pin "4") (pinfunction "4_4") (pintype "bidirectional"))
      (node (ref "J12") (pin "SS1") (pinfunction "SS1_SS1") (pintype "bidirectional"))
      (node (ref "J12") (pin "SS2") (pinfunction "SS2_SS2") (pintype "bidirectional"))
      (node (ref "J13") (pin "4") (pinfunction "4_4") (pintype "bidirectional"))
      (node (ref "J13") (pin "SS1") (pinfunction "SS1_SS1") (pintype "bidirectional"))
      (node (ref "J13") (pin "SS2") (pinfunction "SS2_SS2") (pintype "bidirectional"))
      (node (ref "J14") (pin "4") (pinfunction "4_4") (pintype "bidirectional"))
      (node (ref "J14") (pin "SS1") (pinfunction "SS1_SS1") (pintype "bidirectional"))
      (node (ref "J14") (pin "SS2") (pinfunction "SS2_SS2") (pintype "bidirectional"))
      (node (ref "J5") (pin "2") (pinfunction "P$2_2") (pintype "bidirectional"))
      (node (ref "J6") (pin "5") (pinfunction "GND_5") (pintype "bidirectional"))
      (node (ref "J6") (pin "GND@1") (pinfunction "GND_GND@1") (pintype "bidirectional"))
      (node (ref "J6") (pin "GND@2") (pinfunction "GND_GND@2") (pintype "bidirectional"))
      (node (ref "J6") (pin "GND@3") (pinfunction "GND_GND@3") (pintype "bidirectional"))
      (node (ref "J6") (pin "GND@4") (pinfunction "GND_GND@4") (pintype "bidirectional"))
      (node (ref "K1") (pin "P$2") (pinfunction "2_P$2") (pintype "bidirectional"))
      (node (ref "R11") (pin "1") (pinfunction "1_1") (pintype "passive"))
      (node (ref "R15") (pin "1") (pinfunction "1_1") (pintype "passive"))
      (node (ref "R18") (pin "1") (pinfunction "1_1") (pintype "passive"))
      (node (ref "R2") (pin "1") (pinfunction "1_1") (pintype "passive"))
      (node (ref "R34") (pin "1") (pinfunction "1_1") (pintype "passive"))
      (node (ref "R35") (pin "1") (pinfunction "1_1") (pintype "passive"))
      (node (ref "R36") (pin "1") (pinfunction "1_1") (pintype "passive"))
      (node (ref "R4") (pin "2") (pinfunction "2_2") (pintype "passive"))
      (node (ref "R41") (pin "1") (pinfunction "1_1") (pintype "passive"))
      (node (ref "R7") (pin "1") (pinfunction "1_1") (pintype "passive"))
      (node (ref "S1") (pin "4") (pinfunction "CO_4") (pintype "bidirectional"))
      (node (ref "S2") (pin "4") (pinfunction "CO_4") (pintype "bidirectional"))
      (node (ref "S3") (pin "4") (pinfunction "CO_4") (pintype "bidirectional"))
      (node (ref "S4") (pin "4") (pinfunction "CO_4") (pintype "bidirectional"))
      (node (ref "S5") (pin "4") (pinfunction "CO_4") (pintype "bidirectional"))
      (node (ref "U1") (pin "4") (pinfunction "GND_4") (pintype "power_in"))
      (node (ref "U13") (pin "15") (pinfunction "GND_15") (pintype "bidirectional"))
      (node (ref "U13") (pin "24") (pinfunction "GND_24") (pintype "bidirectional"))
      (node (ref "U13") (pin "25") (pinfunction "GND_25") (pintype "bidirectional"))
      (node (ref "U2") (pin "4") (pinfunction "GND_4") (pintype "power_in"))
      (node (ref "U3") (pin "4") (pinfunction "GND_4") (pintype "power_in"))
      (node (ref "U3") (pin "5") (pinfunction "+IN2_5") (pintype "input"))
      (node (ref "U3") (pin "6") (pinfunction "-IN2_6") (pintype "input"))
      (node (ref "U4") (pin "P$1") (pinfunction "GND_P$1") (pintype "bidirectional"))
      (node (ref "U4") (pin "P$10") (pinfunction "GND_P$10") (pintype "bidirectional"))
      (node (ref "U4") (pin "P$11") (pinfunction "GND_P$11") (pintype "bidirectional"))
      (node (ref "U4") (pin "P$19") (pinfunction "SENSE_B_P$19") (pintype "bidirectional"))
      (node (ref "U4") (pin "P$2") (pinfunction "SENSE_A_P$2") (pintype "bidirectional"))
      (node (ref "U4") (pin "P$20") (pinfunction "GND_P$20") (pintype "bidirectional"))
      (node (ref "U5") (pin "6") (pinfunction "VSS_6") (pintype "power_in"))
      (node (ref "U6") (pin "3") (pinfunction "GND_3") (pintype "bidirectional"))
      (node (ref "U7") (pin "4") (pinfunction "GND_4") (pintype "power_in"))
      (node (ref "U7") (pin "7") (pinfunction "FSEL_7") (pintype "bidirectional"))
      (node (ref "UART") (pin "4") (pinfunction "4_4") (pintype "bidirectional"))
      (node (ref "UART") (pin "SS1") (pinfunction "SS1_SS1") (pintype "bidirectional"))
      (node (ref "UART") (pin "SS2") (pinfunction "SS2_SS2") (pintype "bidirectional"))
    )
    (net (code "43") (name "Net-(C1-Pad+)") (class "Default")
      (node (ref "C1") (pin "+") (pinfunction "+_+") (pintype "passive"))
      (node (ref "C17") (pin "1") (pinfunction "1_1") (pintype "passive"))
      (node (ref "C20") (pin "1") (pinfunction "1_1") (pintype "passive"))
      (node (ref "D22") (pin "-") (pinfunction "-_-") (pintype "passive"))
      (node (ref "L2") (pin "1") (pinfunction "1_1") (pintype "passive"))
      (node (ref "R40") (pin "1") (pinfunction "1_1") (pintype "passive"))
    )
    (net (code "44") (name "Net-(C19-Pad1)") (class "Default")
      (node (ref "C19") (pin "1") (pinfunction "1_1") (pintype "passive"))
      (node (ref "R32") (pin "2") (pinfunction "2_2") (pintype "passive"))
    )
    (net (code "45") (name "Net-(C21-Pad1)") (class "Default")
      (node (ref "C21") (pin "1") (pinfunction "1_1") (pintype "passive"))
      (node (ref "C22") (pin "1") (pinfunction "1_1") (pintype "passive"))
      (node (ref "C23") (pin "+") (pinfunction "+_+") (pintype "passive"))
      (node (ref "D25") (pin "+") (pinfunction "+_+") (pintype "passive"))
      (node (ref "L2") (pin "2") (pinfunction "2_2") (pintype "passive"))
    )
    (net (code "46") (name "Net-(D1-Pad+)") (class "Default")
      (node (ref "D1") (pin "+") (pinfunction "+_+") (pintype "passive"))
      (node (ref "R3") (pin "2") (pinfunction "2_2") (pintype "passive"))
    )
    (net (code "47") (name "Net-(D2-Pad+)") (class "Default")
      (node (ref "D2") (pin "+") (pinfunction "+_+") (pintype "passive"))
      (node (ref "R8") (pin "2") (pinfunction "2_2") (pintype "passive"))
    )
    (net (code "48") (name "Net-(D3-Pad+)") (class "Default")
      (node (ref "D3") (pin "+") (pinfunction "+_+") (pintype "passive"))
      (node (ref "R12") (pin "2") (pinfunction "2_2") (pintype "passive"))
    )
    (net (code "49") (name "Net-(D4-Pad+)") (class "Default")
      (node (ref "D4") (pin "+") (pinfunction "+_+") (pintype "passive"))
      (node (ref "R16") (pin "2") (pinfunction "2_2") (pintype "passive"))
    )
    (net (code "50") (name "Net-(D5-Pad+)") (class "Default")
      (node (ref "D5") (pin "+") (pinfunction "+_+") (pintype "passive"))
      (node (ref "R20") (pin "2") (pinfunction "2_2") (pintype "passive"))
    )
    (net (code "51") (name "Net-(D15-Pad+)") (class "Default")
      (node (ref "D15") (pin "+") (pinfunction "+_+") (pintype "passive"))
      (node (ref "R23") (pin "1") (pinfunction "1_1") (pintype "passive"))
    )
    (net (code "52") (name "Net-(D16-Pad+)") (class "Default")
      (node (ref "D16") (pin "+") (pinfunction "+_+") (pintype "passive"))
      (node (ref "R21") (pin "1") (pinfunction "1_1") (pintype "passive"))
    )
    (net (code "53") (name "Net-(D18-Pad+)") (class "Default")
      (node (ref "D18") (pin "+") (pinfunction "+_+") (pintype "passive"))
      (node (ref "R28") (pin "1") (pinfunction "1_1") (pintype "passive"))
    )
    (net (code "54") (name "Net-(D19-Pad+)") (class "Default")
      (node (ref "D19") (pin "+") (pinfunction "+_+") (pintype "passive"))
      (node (ref "R29") (pin "1") (pinfunction "1_1") (pintype "passive"))
    )
    (net (code "55") (name "Net-(D20-Pad+)") (class "Default")
      (node (ref "D20") (pin "+") (pinfunction "+_+") (pintype "passive"))
      (node (ref "R30") (pin "1") (pinfunction "1_1") (pintype "passive"))
    )
    (net (code "56") (name "Net-(D21-Pad+)") (class "Default")
      (node (ref "D21") (pin "+") (pinfunction "+_+") (pintype "passive"))
      (node (ref "R31") (pin "1") (pinfunction "1_1") (pintype "passive"))
    )
    (net (code "57") (name "Net-(D23-Pad-)") (class "Default")
      (node (ref "D23") (pin "-") (pinfunction "-_-") (pintype "passive"))
      (node (ref "R35") (pin "2") (pinfunction "2_2") (pintype "passive"))
    )
    (net (code "58") (name "Net-(D24-Pad+)") (class "Default")
      (node (ref "D24") (pin "+") (pinfunction "+_+") (pintype "passive"))
      (node (ref "R37") (pin "1") (pinfunction "1_1") (pintype "passive"))
    )
    (net (code "59") (name "Net-(J5-P$1)") (class "Default")
      (node (ref "F1") (pin "2") (pinfunction "2_2") (pintype "bidirectional"))
      (node (ref "J5") (pin "1") (pinfunction "P$1_1") (pintype "bidirectional"))
    )
    (net (code "60") (name "Net-(Q3-G)") (class "Default")
      (node (ref "Q3") (pin "1") (pinfunction "G_1") (pintype "passive"))
      (node (ref "R33") (pin "2") (pinfunction "2_2") (pintype "passive"))
      (node (ref "U5") (pin "7") (pinfunction "CC_7") (pintype "output"))
    )
    (net (code "61") (name "Net-(Q3-S)") (class "Default")
      (node (ref "Q3") (pin "2") (pinfunction "S_2") (pintype "passive"))
      (node (ref "R39") (pin "2") (pinfunction "2_2") (pintype "passive"))
      (node (ref "U5") (pin "1") (pinfunction "SNS_1") (pintype "input"))
    )
    (net (code "62") (name "Net-(R5-Pad2)") (class "Default")
      (node (ref "R5") (pin "2") (pinfunction "2_2") (pintype "passive"))
      (node (ref "SW2") (pin "1") (pinfunction "1_1") (pintype "bidirectional"))
    )
    (net (code "63") (name "Net-(R9-Pad2)") (class "Default")
      (node (ref "R9") (pin "2") (pinfunction "2_2") (pintype "passive"))
      (node (ref "SW2") (pin "2") (pinfunction "2_2") (pintype "bidirectional"))
    )
    (net (code "64") (name "Net-(R13-Pad2)") (class "Default")
      (node (ref "R13") (pin "2") (pinfunction "2_2") (pintype "passive"))
      (node (ref "SW2") (pin "3") (pinfunction "3_3") (pintype "bidirectional"))
    )
    (net (code "65") (name "Net-(R19-Pad2)") (class "Default")
      (node (ref "R19") (pin "2") (pinfunction "2_2") (pintype "passive"))
      (node (ref "SW2") (pin "4") (pinfunction "4_4") (pintype "bidirectional"))
    )
    (net (code "66") (name "Net-(R22-Pad2)") (class "Default")
      (node (ref "R22") (pin "2") (pinfunction "2_2") (pintype "passive"))
      (node (ref "SW2") (pin "5") (pinfunction "5_5") (pintype "bidirectional"))
    )
    (net (code "67") (name "Net-(S1-C)") (class "Default")
      (node (ref "R2") (pin "2") (pinfunction "2_2") (pintype "passive"))
      (node (ref "S1") (pin "2") (pinfunction "C_2") (pintype "bidirectional"))
    )
    (net (code "68") (name "Net-(S1-EM)") (class "Default")
      (node (ref "R1") (pin "1") (pinfunction "1_1") (pintype "passive"))
      (node (ref "S1") (pin "3") (pinfunction "EM_3") (pintype "bidirectional"))
      (node (ref "U2") (pin "2") (pinfunction "-IN1_2") (pintype "input"))
    )
    (net (code "69") (name "Net-(S2-C)") (class "Default")
      (node (ref "R7") (pin "2") (pinfunction "2_2") (pintype "passive"))
      (node (ref "S2") (pin "2") (pinfunction "C_2") (pintype "bidirectional"))
    )
    (net (code "70") (name "Net-(S2-EM)") (class "Default")
      (node (ref "R6") (pin "1") (pinfunction "1_1") (pintype "passive"))
      (node (ref "S2") (pin "3") (pinfunction "EM_3") (pintype "bidirectional"))
      (node (ref "U2") (pin "6") (pinfunction "-IN2_6") (pintype "input"))
    )
    (net (code "71") (name "Net-(S3-C)") (class "Default")
      (node (ref "R11") (pin "2") (pinfunction "2_2") (pintype "passive"))
      (node (ref "S3") (pin "2") (pinfunction "C_2") (pintype "bidirectional"))
    )
    (net (code "72") (name "Net-(S3-EM)") (class "Default")
      (node (ref "R10") (pin "1") (pinfunction "1_1") (pintype "passive"))
      (node (ref "S3") (pin "3") (pinfunction "EM_3") (pintype "bidirectional"))
      (node (ref "U1") (pin "2") (pinfunction "-IN1_2") (pintype "input"))
    )
    (net (code "73") (name "Net-(S4-C)") (class "Default")
      (node (ref "R15") (pin "2") (pinfunction "2_2") (pintype "passive"))
      (node (ref "S4") (pin "2") (pinfunction "C_2") (pintype "bidirectional"))
    )
    (net (code "74") (name "Net-(S4-EM)") (class "Default")
      (node (ref "R14") (pin "1") (pinfunction "1_1") (pintype "passive"))
      (node (ref "S4") (pin "3") (pinfunction "EM_3") (pintype "bidirectional"))
      (node (ref "U1") (pin "6") (pinfunction "-IN2_6") (pintype "input"))
    )
    (net (code "75") (name "Net-(S5-C)") (class "Default")
      (node (ref "R18") (pin "2") (pinfunction "2_2") (pintype "passive"))
      (node (ref "S5") (pin "2") (pinfunction "C_2") (pintype "bidirectional"))
    )
    (net (code "76") (name "Net-(S5-EM)") (class "Default")
      (node (ref "R17") (pin "1") (pinfunction "1_1") (pintype "passive"))
      (node (ref "S5") (pin "3") (pinfunction "EM_3") (pintype "bidirectional"))
      (node (ref "U3") (pin "2") (pinfunction "-IN1_2") (pintype "input"))
    )
    (net (code "77") (name "Net-(U5-STAT)") (class "Default")
      (node (ref "D23") (pin "+") (pinfunction "+_+") (pintype "passive"))
      (node (ref "D24") (pin "-") (pinfunction "-_-") (pintype "passive"))
      (node (ref "R34") (pin "2") (pinfunction "2_2") (pintype "passive"))
      (node (ref "U5") (pin "5") (pinfunction "STAT_5") (pintype "output"))
    )
    (net (code "78") (name "Net-(U5-TS)") (class "Default")
      (node (ref "R36") (pin "2") (pinfunction "2_2") (pintype "passive"))
      (node (ref "R38") (pin "1") (pinfunction "1_1") (pintype "passive"))
      (node (ref "U5") (pin "4") (pinfunction "TS_4") (pintype "input"))
    )
    (net (code "79") (name "Net-(U6-IN)") (class "Default")
      (node (ref "C11") (pin "+") (pinfunction "+_+") (pintype "passive"))
      (node (ref "D14") (pin "-") (pinfunction "-_-") (pintype "passive"))
      (node (ref "U6") (pin "1") (pinfunction "IN_1") (pintype "bidirectional"))
    )
    (net (code "80") (name "Net-(U7-COMP)") (class "Default")
      (node (ref "R32") (pin "1") (pinfunction "1_1") (pintype "passive"))
      (node (ref "U7") (pin "1") (pinfunction "COMP_1") (pintype "bidirectional"))
    )
    (net (code "81") (name "Net-(U7-FB)") (class "Default")
      (node (ref "R40") (pin "2") (pinfunction "2_2") (pintype "passive"))
      (node (ref "R41") (pin "2") (pinfunction "2_2") (pintype "passive"))
      (node (ref "U7") (pin "2") (pinfunction "FB_2") (pintype "input"))
    )
    (net (code "82") (name "Net-(U7-LX)") (class "Default")
      (node (ref "D22") (pin "+") (pinfunction "+_+") (pintype "passive"))
      (node (ref "L1") (pin "1") (pinfunction "1_1") (pintype "passive"))
      (node (ref "U7") (pin "5") (pinfunction "LX_5") (pintype "output"))
    )
    (net (code "83") (name "Net-(U7-SS)") (class "Default")
      (node (ref "C18") (pin "1") (pinfunction "1_1") (pintype "passive"))
      (node (ref "U7") (pin "8") (pinfunction "SS_8") (pintype "bidirectional"))
    )
    (net (code "84") (name "unconnected-(J6-DM-Pad2)") (class "Default")
      (node (ref "J6") (pin "2") (pinfunction "DM_2") (pintype "bidirectional"))
    )
    (net (code "85") (name "unconnected-(J6-DP-Pad3)") (class "Default")
      (node (ref "J6") (pin "3") (pinfunction "DP_3") (pintype "bidirectional"))
    )
    (net (code "86") (name "unconnected-(J6-ID-Pad4)") (class "Default")
      (node (ref "J6") (pin "4") (pinfunction "ID_4") (pintype "bidirectional"))
    )
    (net (code "87") (name "unconnected-(SW1-PadCH1B)") (class "Default")
      (node (ref "SW1") (pin "CH1B") (pinfunction "CH1B_CH1B") (pintype "bidirectional"))
    )
    (net (code "88") (name "unconnected-(SW1-PadCH2B)") (class "Default")
      (node (ref "SW1") (pin "CH2B") (pinfunction "CH2B_CH2B") (pintype "bidirectional"))
    )
    (net (code "89") (name "unconnected-(U3B-OUT2-Pad7)") (class "Default")
      (node (ref "U3") (pin "7") (pinfunction "OUT2_7") (pintype "output"))
    )
    (net (code "90") (name "unconnected-(U4-NC-PadP$3)") (class "Default")
      (node (ref "U4") (pin "P$3") (pinfunction "NC_P$3") (pintype "bidirectional"))
    )
    (net (code "91") (name "unconnected-(U4-NC-PadP$18)") (class "Default")
      (node (ref "U4") (pin "P$18") (pinfunction "NC_P$18") (pintype "bidirectional"))
    )
    (net (code "92") (name "unconnected-(U13-GND-Pad33)") (class "Default")
      (node (ref "U13") (pin "33") (pinfunction "GND_33") (pintype "bidirectional"))
    )
    (net (code "93") (name "unconnected-(U13-MISO-Pad36)") (class "Default")
      (node (ref "U13") (pin "36") (pinfunction "MISO_36") (pintype "bidirectional"))
    )
    (net (code "94") (name "unconnected-(U13-MOSI-Pad32)") (class "Default")
      (node (ref "U13") (pin "32") (pinfunction "MOSI_32") (pintype "bidirectional"))
    )
    (net (code "95") (name "unconnected-(U13-RST-Pad34)") (class "Default")
      (node (ref "U13") (pin "34") (pinfunction "RST_34") (pintype "bidirectional"))
    )
    (net (code "96") (name "unconnected-(U13-SCK-Pad35)") (class "Default")
      (node (ref "U13") (pin "35") (pinfunction "SCK_35") (pintype "bidirectional"))
    )
    (net (code "97") (name "unconnected-(U13-VCC-Pad31)") (class "Default")
      (node (ref "U13") (pin "31") (pinfunction "VCC_31") (pintype "bidirectional"))
    )
  )
)
